# Circiut.net
KiCad netlist of a schematic drawn in Altium Designer
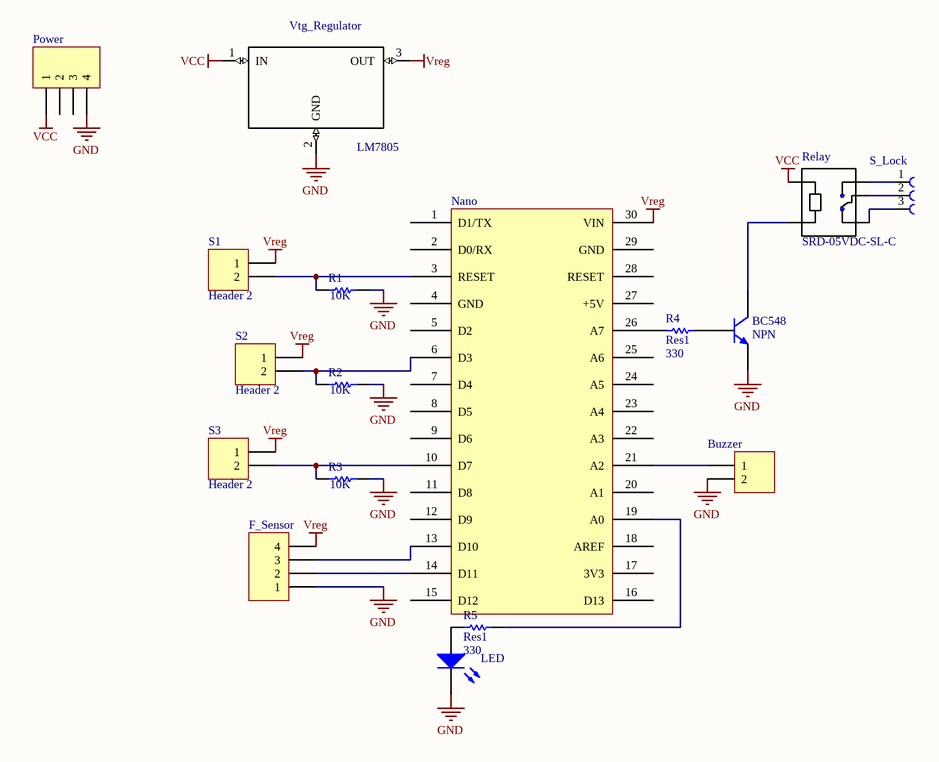
[diagram p0: Circiut.SchDoc]

(export (version "E")
  (design (tool "Eeschema 10.0.6"))
  (components
    (comp (ref "BC548")
      (value "NPN")
      (footprint "TO-226-AA")
      (description "NPN Bipolar Transistor")
      (fields (field (name "PUBLISHER") "Altium Limited"))
      (libsource (lib "Miscellaneous Devices") (part "NPN"))
    )
    (comp (ref "Buzzer")
      (value "Header 2")
      (footprint "HDR1X2")
      (description "Header, 2-Pin")
      (fields (field (name "PUBLISHER") "Altium Limited"))
      (libsource (lib "Miscellaneous Connectors") (part "Header 2"))
    )
    (comp (ref "F_Sensor")
      (value "Header 4")
      (footprint "HDR1X4")
      (description "Header, 4-Pin")
      (fields (field (name "PUBLISHER") "Altium Limited"))
      (libsource (lib "Miscellaneous Connectors") (part "Header 4"))
    )
    (comp (ref "LED")
      (value "LED0")
      (footprint "LED-0")
      (description "Typical INFRARED GaAs LED")
      (fields (field (name "PUBLISHER") "Altium Limited"))
      (libsource (lib "Miscellaneous Devices") (part "LED0"))
    )
    (comp (ref "Nano") (value "ARDUINO NANO") (footprint "NANO") (libsource (lib "TRAINING") (part "NANO")))
    (comp (ref "Power")
      (value "Header 4")
      (footprint "HDR1X4")
      (description "Header, 4-Pin")
      (fields (field (name "PUBLISHER") "Altium Limited"))
      (libsource (lib "") (part "Header 4_1"))
    )
    (comp (ref "R1")
      (value "10K")
      (footprint "AXIAL-0.3")
      (description "Resistor")
      (fields (field (name "Comment") "Res1") (field (name "PUBLISHER") "Altium Limited"))
      (libsource (lib "Miscellaneous Devices") (part "Res1"))
    )
    (comp (ref "R2")
      (value "10K")
      (footprint "AXIAL-0.3")
      (description "Resistor")
      (fields (field (name "Comment") "Res1") (field (name "PUBLISHER") "Altium Limited"))
      (libsource (lib "Miscellaneous Devices") (part "Res1"))
    )
    (comp (ref "R3")
      (value "10K")
      (footprint "AXIAL-0.3")
      (description "Resistor")
      (fields (field (name "Comment") "Res1") (field (name "PUBLISHER") "Altium Limited"))
      (libsource (lib "Miscellaneous Devices") (part "Res1"))
    )
    (comp (ref "R4")
      (value "Res1")
      (footprint "AXIAL-0.3")
      (description "Resistor")
      (fields (field (name "ALTIUM_VALUE") "330") (field (name "PUBLISHER") "Altium Limited"))
      (libsource (lib "Miscellaneous Devices") (part "Res1"))
    )
    (comp (ref "R5")
      (value "Res1")
      (footprint "AXIAL-0.3")
      (description "Resistor")
      (fields (field (name "ALTIUM_VALUE") "330") (field (name "PUBLISHER") "Altium Limited"))
      (libsource (lib "Miscellaneous Devices") (part "Res1"))
    )
    (comp (ref "Relay")
      (value "SRD-05VDC-SL-C")
      (footprint "*RELAY_SRD-05VDC-SL-C_SRD-05VDC-SL-C(Primary)")
      (fields (field (name "MF") "Songle Relay"))
      (libsource (lib "SRD-05VDC-SL-C") (part "SRD-05VDC-SL-C"))
    )
    (comp (ref "S1")
      (value "Header 2")
      (footprint "HDR1X2")
      (description "Header, 2-Pin")
      (fields (field (name "PUBLISHER") "Altium Limited"))
      (libsource (lib "") (part "Header 2_1"))
    )
    (comp (ref "S2")
      (value "Header 2")
      (footprint "HDR1X2")
      (description "Header, 2-Pin")
      (fields (field (name "PUBLISHER") "Altium Limited"))
      (libsource (lib "") (part "Header 2_1"))
    )
    (comp (ref "S3")
      (value "Header 2")
      (footprint "HDR1X2")
      (description "Header, 2-Pin")
      (fields (field (name "PUBLISHER") "Altium Limited"))
      (libsource (lib "") (part "Header 2_1"))
    )
    (comp (ref "S_Lock")
      (value "691214110003")
      (footprint "*691214110003")
      (description "3 Position Wire to Board Terminal Block Horizontal with Board 0.138 _3.50mm_ Through Hole")
      (fields (field (name "MF") "Wurth Electronics"))
      (libsource (lib "691214110003") (part "691214110003"))
    )
    (comp (ref "Vtg_Regulator")
      (value "LM7805")
      (footprint "*TO220")
      (description "Linear Voltage Regulator IC 1 Output 1.5A SOT-223-4")
      (fields (field (name "MF") "Texas Instruments"))
      (libsource (lib "LM7805") (part "LM7805"))
    )
  )
  (nets
    (net (code "1") (name "GND") (class "Default")
      (node (ref "BC548") (pin "3") (pinfunction "E_3") (pintype "passive"))
      (node (ref "Buzzer") (pin "2") (pinfunction "2_2") (pintype "passive"))
      (node (ref "F_Sensor") (pin "1") (pinfunction "1_1") (pintype "passive"))
      (node (ref "LED") (pin "1") (pinfunction "A_1") (pintype "passive"))
      (node (ref "Power") (pin "4") (pinfunction "4_4") (pintype "passive"))
      (node (ref "R1") (pin "2") (pinfunction "2_2") (pintype "passive"))
      (node (ref "R2") (pin "2") (pinfunction "2_2") (pintype "passive"))
      (node (ref "R3") (pin "2") (pinfunction "2_2") (pintype "passive"))
      (node (ref "Vtg_Regulator") (pin "2") (pinfunction "GND_2") (pintype "bidirectional"))
    )
    (net (code "2") (name "Net-(BC548-B)") (class "Default")
      (node (ref "BC548") (pin "2") (pinfunction "B_2") (pintype "passive"))
      (node (ref "R4") (pin "2") (pinfunction "2_2") (pintype "passive"))
    )
    (net (code "3") (name "Net-(BC548-C)") (class "Default")
      (node (ref "BC548") (pin "1") (pinfunction "C_1") (pintype "passive"))
      (node (ref "Relay") (pin "A2") (pinfunction "A2_A2") (pintype "passive"))
    )
    (net (code "4") (name "Net-(LED-K)") (class "Default")
      (node (ref "LED") (pin "2") (pinfunction "K_2") (pintype "passive"))
      (node (ref "R5") (pin "1") (pinfunction "1_1") (pintype "passive"))
    )
    (net (code "5") (name "Net-(Nano-A0)") (class "Default")
      (node (ref "Nano") (pin "19") (pinfunction "A0_19") (pintype "passive"))
      (node (ref "R5") (pin "2") (pinfunction "2_2") (pintype "passive"))
    )
    (net (code "6") (name "Net-(Nano-A2)") (class "Default")
      (node (ref "Buzzer") (pin "1") (pinfunction "1_1") (pintype "passive"))
      (node (ref "Nano") (pin "21") (pinfunction "A2_21") (pintype "passive"))
    )
    (net (code "7") (name "Net-(Nano-A7)") (class "Default")
      (node (ref "Nano") (pin "26") (pinfunction "A7_26") (pintype "passive"))
      (node (ref "R4") (pin "1") (pinfunction "1_1") (pintype "passive"))
    )
    (net (code "8") (name "Net-(Nano-D3)") (class "Default")
      (node (ref "Nano") (pin "6") (pinfunction "D3_6") (pintype "passive"))
      (node (ref "R2") (pin "1") (pinfunction "1_1") (pintype "passive"))
      (node (ref "S2") (pin "2") (pinfunction "2_2") (pintype "passive"))
    )
    (net (code "9") (name "Net-(Nano-D7)") (class "Default")
      (node (ref "Nano") (pin "10") (pinfunction "D7_10") (pintype "passive"))
      (node (ref "R3") (pin "1") (pinfunction "1_1") (pintype "passive"))
      (node (ref "S3") (pin "2") (pinfunction "2_2") (pintype "passive"))
    )
    (net (code "10") (name "Net-(Nano-D10)") (class "Default")
      (node (ref "F_Sensor") (pin "3") (pinfunction "3_3") (pintype "passive"))
      (node (ref "Nano") (pin "13") (pinfunction "D10_13") (pintype "passive"))
    )
    (net (code "11") (name "Net-(Nano-D11)") (class "Default")
      (node (ref "F_Sensor") (pin "2") (pinfunction "2_2") (pintype "passive"))
      (node (ref "Nano") (pin "14") (pinfunction "D11_14") (pintype "passive"))
    )
    (net (code "12") (name "Net-(Nano-RESET-Pad3)") (class "Default")
      (node (ref "Nano") (pin "3") (pinfunction "RESET_3") (pintype "passive"))
      (node (ref "R1") (pin "1") (pinfunction "1_1") (pintype "passive"))
      (node (ref "S1") (pin "2") (pinfunction "2_2") (pintype "passive"))
    )
    (net (code "13") (name "Net-(Relay-PadCOM)") (class "Default")
      (node (ref "Relay") (pin "COM") (pinfunction "COM_COM") (pintype "passive"))
      (node (ref "S_Lock") (pin "2") (pinfunction "2_2") (pintype "passive"))
    )
    (net (code "14") (name "Net-(Relay-PadNC)") (class "Default")
      (node (ref "Relay") (pin "NC") (pinfunction "NC_NC") (pintype "passive"))
      (node (ref "S_Lock") (pin "3") (pinfunction "3_3") (pintype "passive"))
    )
    (net (code "15") (name "Net-(Relay-PadNO)") (class "Default")
      (node (ref "Relay") (pin "NO") (pinfunction "NO_NO") (pintype "passive"))
      (node (ref "S_Lock") (pin "1") (pinfunction "1_1") (pintype "passive"))
    )
    (net (code "16") (name "VCC") (class "Default")
      (node (ref "Power") (pin "1") (pinfunction "1_1") (pintype "passive"))
      (node (ref "Relay") (pin "A1") (pinfunction "A1_A1") (pintype "passive"))
      (node (ref "Vtg_Regulator") (pin "1") (pinfunction "IN_1") (pintype "bidirectional"))
    )
    (net (code "17") (name "Vreg") (class "Default")
      (node (ref "F_Sensor") (pin "4") (pinfunction "4_4") (pintype "passive"))
      (node (ref "Nano") (pin "30") (pinfunction "VIN_30") (pintype "passive"))
      (node (ref "S1") (pin "1") (pinfunction "1_1") (pintype "passive"))
      (node (ref "S2") (pin "1") (pinfunction "1_1") (pintype "passive"))
      (node (ref "S3") (pin "1") (pinfunction "1_1") (pintype "passive"))
      (node (ref "Vtg_Regulator") (pin "3") (pinfunction "OUT_3") (pintype "bidirectional"))
    )
    (net (code "18") (name "unconnected-(Nano-+5V-Pad27)") (class "Default")
      (node (ref "Nano") (pin "27") (pinfunction "+5V_27") (pintype "passive"))
    )
    (net (code "19") (name "unconnected-(Nano-3V3-Pad17)") (class "Default")
      (node (ref "Nano") (pin "17") (pinfunction "3V3_17") (pintype "passive"))
    )
    (net (code "20") (name "unconnected-(Nano-A1-Pad20)") (class "Default")
      (node (ref "Nano") (pin "20") (pinfunction "A1_20") (pintype "passive"))
    )
    (net (code "21") (name "unconnected-(Nano-A3-Pad22)") (class "Default")
      (node (ref "Nano") (pin "22") (pinfunction "A3_22") (pintype "passive"))
    )
    (net (code "22") (name "unconnected-(Nano-A4-Pad23)") (class "Default")
      (node (ref "Nano") (pin "23") (pinfunction "A4_23") (pintype "passive"))
    )
    (net (code "23") (name "unconnected-(Nano-A5-Pad24)") (class "Default")
      (node (ref "Nano") (pin "24") (pinfunction "A5_24") (pintype "passive"))
    )
    (net (code "24") (name "unconnected-(Nano-A6-Pad25)") (class "Default")
      (node (ref "Nano") (pin "25") (pinfunction "A6_25") (pintype "passive"))
    )
    (net (code "25") (name "unconnected-(Nano-AREF-Pad18)") (class "Default")
      (node (ref "Nano") (pin "18") (pinfunction "AREF_18") (pintype "passive"))
    )
    (net (code "26") (name "unconnected-(Nano-D0{slash}RX-Pad2)") (class "Default")
      (node (ref "Nano") (pin "2") (pinfunction "D0/RX_2") (pintype "passive"))
    )
    (net (code "27") (name "unconnected-(Nano-D1{slash}TX-Pad1)") (class "Default")
      (node (ref "Nano") (pin "1") (pinfunction "D1/TX_1") (pintype "passive"))
    )
    (net (code "28") (name "unconnected-(Nano-D2-Pad5)") (class "Default")
      (node (ref "Nano") (pin "5") (pinfunction "D2_5") (pintype "passive"))
    )
    (net (code "29") (name "unconnected-(Nano-D4-Pad7)") (class "Default")
      (node (ref "Nano") (pin "7") (pinfunction "D4_7") (pintype "passive"))
    )
    (net (code "30") (name "unconnected-(Nano-D5-Pad8)") (class "Default")
      (node (ref "Nano") (pin "8") (pinfunction "D5_8") (pintype "passive"))
    )
    (net (code "31") (name "unconnected-(Nano-D6-Pad9)") (class "Default")
      (node (ref "Nano") (pin "9") (pinfunction "D6_9") (pintype "passive"))
    )
    (net (code "32") (name "unconnected-(Nano-D8-Pad11)") (class "Default")
      (node (ref "Nano") (pin "11") (pinfunction "D8_11") (pintype "passive"))
    )
    (net (code "33") (name "unconnected-(Nano-D9-Pad12)") (class "Default")
      (node (ref "Nano") (pin "12") (pinfunction "D9_12") (pintype "passive"))
    )
    (net (code "34") (name "unconnected-(Nano-D12-Pad15)") (class "Default")
      (node (ref "Nano") (pin "15") (pinfunction "D12_15") (pintype "passive"))
    )
    (net (code "35") (name "unconnected-(Nano-D13-Pad16)") (class "Default")
      (node (ref "Nano") (pin "16") (pinfunction "D13_16") (pintype "passive"))
    )
    (net (code "36") (name "unconnected-(Nano-GND-Pad4)") (class "Default")
      (node (ref "Nano") (pin "4") (pinfunction "GND_4") (pintype "passive"))
    )
    (net (code "37") (name "unconnected-(Nano-GND-Pad29)") (class "Default")
      (node (ref "Nano") (pin "29") (pinfunction "GND_29") (pintype "passive"))
    )
    (net (code "38") (name "unconnected-(Nano-RESET-Pad28)") (class "Default")
      (node (ref "Nano") (pin "28") (pinfunction "RESET_28") (pintype "passive"))
    )
    (net (code "39") (name "unconnected-(Power-Pad2)") (class "Default")
      (node (ref "Power") (pin "2") (pinfunction "2_2") (pintype "passive"))
    )
    (net (code "40") (name "unconnected-(Power-Pad3)") (class "Default")
      (node (ref "Power") (pin "3") (pinfunction "3_3") (pintype "passive"))
    )
  )
)
